# stl_mainboard.net
KiCad netlist of a schematic drawn in EAGLE
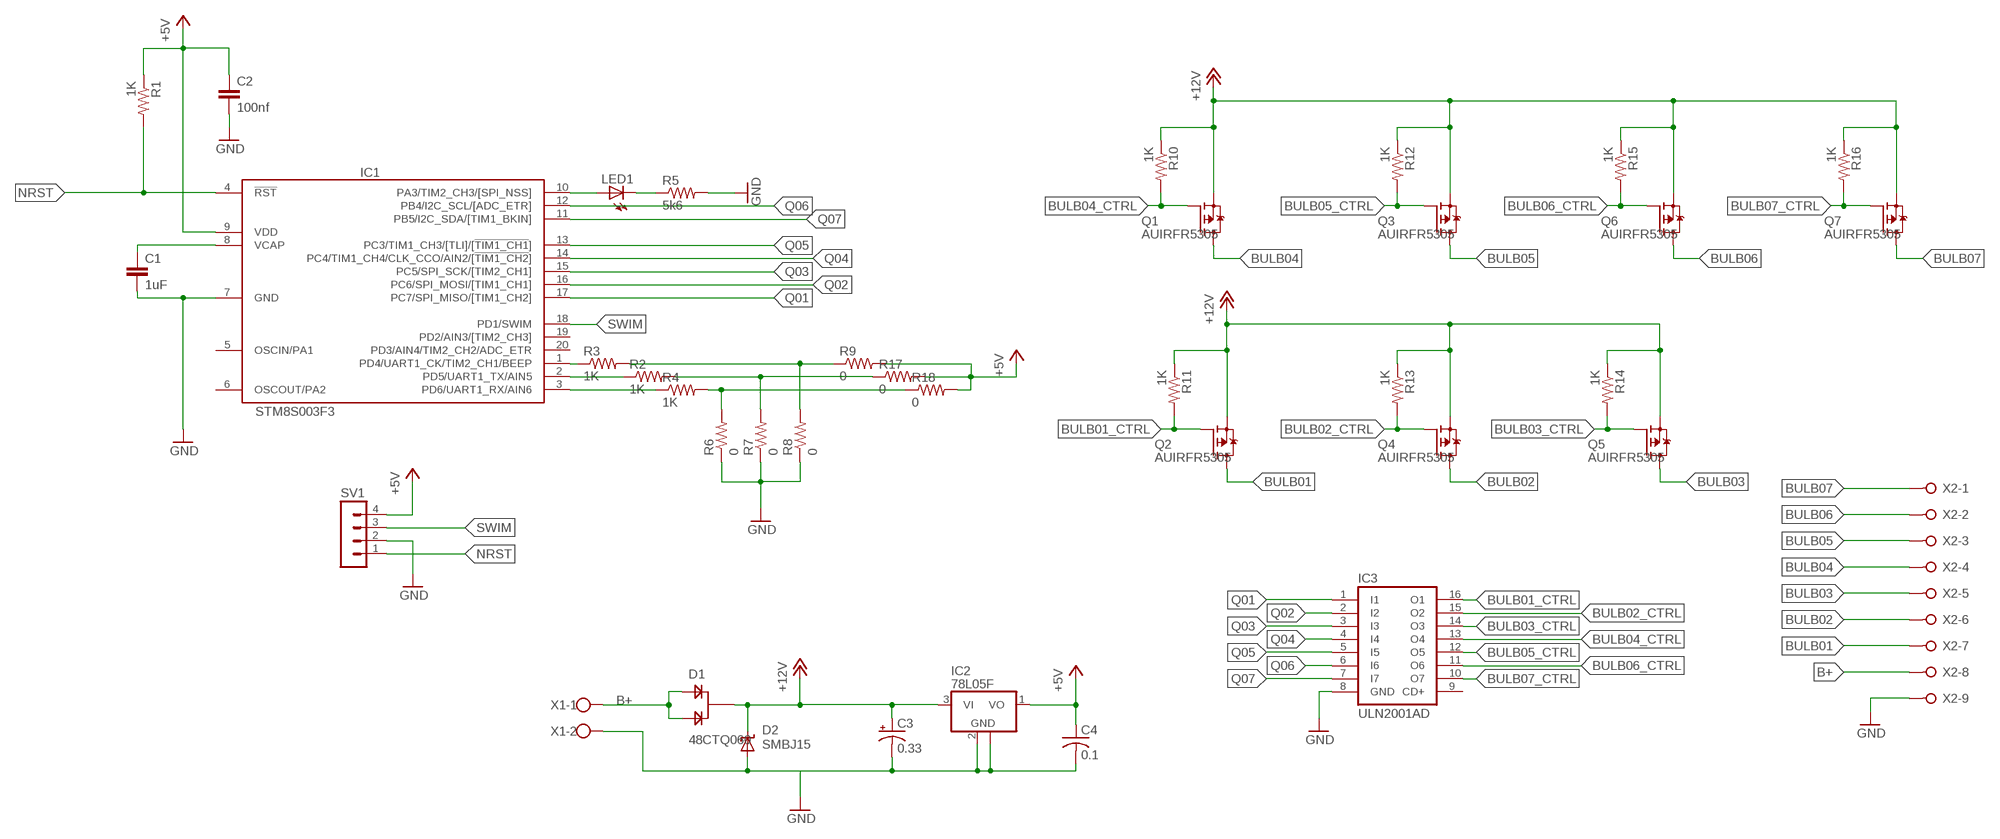
[diagram p0: schematic, sheet 1]

(export (version "E")
  (design (tool "Eeschema 10.0.6"))
  (components
    (comp (ref "C1")
      (value "1uF")
      (footprint "eagle-import:C1206")
      (libsource (lib "eagle-import") (part "C-EUC1206"))
    )
    (comp (ref "C2")
      (value "100nf")
      (footprint "eagle-import:C1206")
      (libsource (lib "eagle-import") (part "C-EUC1206"))
    )
    (comp (ref "C3")
      (value "0.33")
      (footprint "eagle-import:E5-8,5")
      (libsource (lib "eagle-import") (part "CPOL-USE5-8.5"))
    )
    (comp (ref "C4")
      (value "0.1")
      (footprint "eagle-import:C0805")
      (libsource (lib "eagle-import") (part "C-USC0805"))
    )
    (comp (ref "D1")
      (value "48CTQ060")
      (footprint "eagle-import:TO263AB")
      (libsource (lib "eagle-import") (part "48CTQ060"))
    )
    (comp (ref "D2")
      (value "SMBJ15")
      (footprint "eagle-import:SMBJ")
      (libsource (lib "eagle-import") (part "SUPPRESSOR-SMBJ"))
    )
    (comp (ref "IC1")
      (value "STM8S003F3")
      (footprint "eagle-import:TSSOP20")
      (libsource (lib "eagle-import") (part "STM8S003F3"))
    )
    (comp (ref "IC2")
      (value "78L05F")
      (footprint "eagle-import:SOT89")
      (libsource (lib "eagle-import") (part "78LF05"))
    )
    (comp (ref "IC3")
      (value "ULN2001AD")
      (footprint "eagle-import:SO16")
      (libsource (lib "eagle-import") (part "ULN2001AD"))
    )
    (comp (ref "LED1")
      (value "LEDSML1206")
      (footprint "eagle-import:SML1206")
      (libsource (lib "eagle-import") (part "LEDSML1206"))
    )
    (comp (ref "Q1")
      (value "AUIRFR5305")
      (footprint "eagle-import:TO252")
      (libsource (lib "eagle-import") (part "SPD30P06PTO252"))
    )
    (comp (ref "Q2")
      (value "AUIRFR5305")
      (footprint "eagle-import:TO252")
      (libsource (lib "eagle-import") (part "SPD30P06PTO252"))
    )
    (comp (ref "Q3")
      (value "AUIRFR5305")
      (footprint "eagle-import:TO252")
      (libsource (lib "eagle-import") (part "SPD30P06PTO252"))
    )
    (comp (ref "Q4")
      (value "AUIRFR5305")
      (footprint "eagle-import:TO252")
      (libsource (lib "eagle-import") (part "SPD30P06PTO252"))
    )
    (comp (ref "Q5")
      (value "AUIRFR5305")
      (footprint "eagle-import:TO252")
      (libsource (lib "eagle-import") (part "SPD30P06PTO252"))
    )
    (comp (ref "Q6")
      (value "AUIRFR5305")
      (footprint "eagle-import:TO252")
      (libsource (lib "eagle-import") (part "SPD30P06PTO252"))
    )
    (comp (ref "Q7")
      (value "AUIRFR5305")
      (footprint "eagle-import:TO252")
      (libsource (lib "eagle-import") (part "SPD30P06PTO252"))
    )
    (comp (ref "R1")
      (value "1K")
      (footprint "eagle-import:M0805")
      (libsource (lib "eagle-import") (part "R-US_M0805"))
    )
    (comp (ref "R2")
      (value "1K")
      (footprint "eagle-import:M0805")
      (libsource (lib "eagle-import") (part "R-US_M0805"))
    )
    (comp (ref "R3")
      (value "1K")
      (footprint "eagle-import:M0805")
      (libsource (lib "eagle-import") (part "R-US_M0805"))
    )
    (comp (ref "R4")
      (value "1K")
      (footprint "eagle-import:M0805")
      (libsource (lib "eagle-import") (part "R-US_M0805"))
    )
    (comp (ref "R5")
      (value "5k6")
      (footprint "eagle-import:M0805")
      (libsource (lib "eagle-import") (part "R-US_M0805"))
    )
    (comp (ref "R6")
      (value "0")
      (footprint "eagle-import:M0805")
      (libsource (lib "eagle-import") (part "R-US_M0805"))
    )
    (comp (ref "R7")
      (value "0")
      (footprint "eagle-import:M0805")
      (libsource (lib "eagle-import") (part "R-US_M0805"))
    )
    (comp (ref "R8")
      (value "0")
      (footprint "eagle-import:M0805")
      (libsource (lib "eagle-import") (part "R-US_M0805"))
    )
    (comp (ref "R9")
      (value "0")
      (footprint "eagle-import:M0805")
      (libsource (lib "eagle-import") (part "R-US_M0805"))
    )
    (comp (ref "R10")
      (value "1K")
      (footprint "eagle-import:M0805")
      (libsource (lib "eagle-import") (part "R-US_M0805"))
    )
    (comp (ref "R11")
      (value "1K")
      (footprint "eagle-import:M0805")
      (libsource (lib "eagle-import") (part "R-US_M0805"))
    )
    (comp (ref "R12")
      (value "1K")
      (footprint "eagle-import:M0805")
      (libsource (lib "eagle-import") (part "R-US_M0805"))
    )
    (comp (ref "R13")
      (value "1K")
      (footprint "eagle-import:M0805")
      (libsource (lib "eagle-import") (part "R-US_M0805"))
    )
    (comp (ref "R14")
      (value "1K")
      (footprint "eagle-import:M0805")
      (libsource (lib "eagle-import") (part "R-US_M0805"))
    )
    (comp (ref "R15")
      (value "1K")
      (footprint "eagle-import:M0805")
      (libsource (lib "eagle-import") (part "R-US_M0805"))
    )
    (comp (ref "R16")
      (value "1K")
      (footprint "eagle-import:M0805")
      (libsource (lib "eagle-import") (part "R-US_M0805"))
    )
    (comp (ref "R17")
      (value "0")
      (footprint "eagle-import:M0805")
      (libsource (lib "eagle-import") (part "R-US_M0805"))
    )
    (comp (ref "R18")
      (value "0")
      (footprint "eagle-import:M0805")
      (libsource (lib "eagle-import") (part "R-US_M0805"))
    )
    (comp (ref "SV1")
      (value "MA04-1")
      (footprint "eagle-import:MA04-1")
      (libsource (lib "eagle-import") (part "MA04-1"))
    )
    (comp (ref "X1")
      (value "W237-102")
      (footprint "eagle-import:W237-102")
      (fields (field (name "MPN") "237-102"))
      (libsource (lib "eagle-import") (part "W237-102"))
    )
    (comp (ref "X2")
      (value "W237-09P")
      (footprint "eagle-import:W237-9P")
      (libsource (lib "eagle-import") (part "W237-09P"))
    )
  )
  (nets
    (net (code "1") (name "+5V") (class "Default")
      (node (ref "C2") (pin "1") (pinfunction "1_1") (pintype "passive"))
      (node (ref "C4") (pin "1") (pinfunction "1_1") (pintype "passive"))
      (node (ref "IC1") (pin "9") (pinfunction "VDD_9") (pintype "power_in"))
      (node (ref "IC2") (pin "1") (pinfunction "VO_1") (pintype "passive"))
      (node (ref "R1") (pin "1") (pinfunction "1_1") (pintype "passive"))
      (node (ref "R17") (pin "2") (pinfunction "2_2") (pintype "passive"))
      (node (ref "R18") (pin "2") (pinfunction "2_2") (pintype "passive"))
      (node (ref "R9") (pin "2") (pinfunction "2_2") (pintype "passive"))
      (node (ref "SV1") (pin "4") (pinfunction "4_4") (pintype "passive"))
    )
    (net (code "2") (name "+12V") (class "Default")
      (node (ref "C3") (pin "+") (pinfunction "+_+") (pintype "passive"))
      (node (ref "D1") (pin "K") (pinfunction "P$1_K") (pintype "bidirectional"))
      (node (ref "D2") (pin "C") (pinfunction "C_C") (pintype "passive"))
      (node (ref "IC2") (pin "3") (pinfunction "VI_3") (pintype "input"))
      (node (ref "Q1") (pin "2") (pinfunction "S_2") (pintype "passive"))
      (node (ref "Q2") (pin "2") (pinfunction "S_2") (pintype "passive"))
      (node (ref "Q3") (pin "2") (pinfunction "S_2") (pintype "passive"))
      (node (ref "Q4") (pin "2") (pinfunction "S_2") (pintype "passive"))
      (node (ref "Q5") (pin "2") (pinfunction "S_2") (pintype "passive"))
      (node (ref "Q6") (pin "2") (pinfunction "S_2") (pintype "passive"))
      (node (ref "Q7") (pin "2") (pinfunction "S_2") (pintype "passive"))
      (node (ref "R10") (pin "1") (pinfunction "1_1") (pintype "passive"))
      (node (ref "R11") (pin "1") (pinfunction "1_1") (pintype "passive"))
      (node (ref "R12") (pin "1") (pinfunction "1_1") (pintype "passive"))
      (node (ref "R13") (pin "1") (pinfunction "1_1") (pintype "passive"))
      (node (ref "R14") (pin "1") (pinfunction "1_1") (pintype "passive"))
      (node (ref "R15") (pin "1") (pinfunction "1_1") (pintype "passive"))
      (node (ref "R16") (pin "1") (pinfunction "1_1") (pintype "passive"))
    )
    (net (code "3") (name "B+") (class "Default")
      (node (ref "D1") (pin "1") (pinfunction "P$2_1") (pintype "bidirectional"))
      (node (ref "D1") (pin "2") (pinfunction "P$3_2") (pintype "bidirectional"))
      (node (ref "X1") (pin "1") (pinfunction "KL_1") (pintype "passive"))
      (node (ref "X2") (pin "8") (pinfunction "KL_8") (pintype "passive"))
    )
    (net (code "4") (name "BULB01") (class "Default")
      (node (ref "Q2") (pin "3") (pinfunction "D_3") (pintype "passive"))
      (node (ref "X2") (pin "7") (pinfunction "KL_7") (pintype "passive"))
    )
    (net (code "5") (name "BULB01_CTRL") (class "Default")
      (node (ref "IC3") (pin "16") (pinfunction "O1_16") (pintype "open_collector"))
      (node (ref "Q2") (pin "1") (pinfunction "G_1") (pintype "passive"))
      (node (ref "R11") (pin "2") (pinfunction "2_2") (pintype "passive"))
    )
    (net (code "6") (name "BULB02") (class "Default")
      (node (ref "Q4") (pin "3") (pinfunction "D_3") (pintype "passive"))
      (node (ref "X2") (pin "6") (pinfunction "KL_6") (pintype "passive"))
    )
    (net (code "7") (name "BULB02_CTRL") (class "Default")
      (node (ref "IC3") (pin "15") (pinfunction "O2_15") (pintype "open_collector"))
      (node (ref "Q4") (pin "1") (pinfunction "G_1") (pintype "passive"))
      (node (ref "R13") (pin "2") (pinfunction "2_2") (pintype "passive"))
    )
    (net (code "8") (name "BULB03") (class "Default")
      (node (ref "Q5") (pin "3") (pinfunction "D_3") (pintype "passive"))
      (node (ref "X2") (pin "5") (pinfunction "KL_5") (pintype "passive"))
    )
    (net (code "9") (name "BULB03_CTRL") (class "Default")
      (node (ref "IC3") (pin "14") (pinfunction "O3_14") (pintype "open_collector"))
      (node (ref "Q5") (pin "1") (pinfunction "G_1") (pintype "passive"))
      (node (ref "R14") (pin "2") (pinfunction "2_2") (pintype "passive"))
    )
    (net (code "10") (name "BULB04") (class "Default")
      (node (ref "Q1") (pin "3") (pinfunction "D_3") (pintype "passive"))
      (node (ref "X2") (pin "4") (pinfunction "KL_4") (pintype "passive"))
    )
    (net (code "11") (name "BULB04_CTRL") (class "Default")
      (node (ref "IC3") (pin "13") (pinfunction "O4_13") (pintype "open_collector"))
      (node (ref "Q1") (pin "1") (pinfunction "G_1") (pintype "passive"))
      (node (ref "R10") (pin "2") (pinfunction "2_2") (pintype "passive"))
    )
    (net (code "12") (name "BULB05") (class "Default")
      (node (ref "Q3") (pin "3") (pinfunction "D_3") (pintype "passive"))
      (node (ref "X2") (pin "3") (pinfunction "KL_3") (pintype "passive"))
    )
    (net (code "13") (name "BULB05_CTRL") (class "Default")
      (node (ref "IC3") (pin "12") (pinfunction "O5_12") (pintype "open_collector"))
      (node (ref "Q3") (pin "1") (pinfunction "G_1") (pintype "passive"))
      (node (ref "R12") (pin "2") (pinfunction "2_2") (pintype "passive"))
    )
    (net (code "14") (name "BULB06") (class "Default")
      (node (ref "Q6") (pin "3") (pinfunction "D_3") (pintype "passive"))
      (node (ref "X2") (pin "2") (pinfunction "KL_2") (pintype "passive"))
    )
    (net (code "15") (name "BULB06_CTRL") (class "Default")
      (node (ref "IC3") (pin "11") (pinfunction "O6_11") (pintype "open_collector"))
      (node (ref "Q6") (pin "1") (pinfunction "G_1") (pintype "passive"))
      (node (ref "R15") (pin "2") (pinfunction "2_2") (pintype "passive"))
    )
    (net (code "16") (name "BULB07") (class "Default")
      (node (ref "Q7") (pin "3") (pinfunction "D_3") (pintype "passive"))
      (node (ref "X2") (pin "1") (pinfunction "KL_1") (pintype "passive"))
    )
    (net (code "17") (name "BULB07_CTRL") (class "Default")
      (node (ref "IC3") (pin "10") (pinfunction "O7_10") (pintype "open_collector"))
      (node (ref "Q7") (pin "1") (pinfunction "G_1") (pintype "passive"))
      (node (ref "R16") (pin "2") (pinfunction "2_2") (pintype "passive"))
    )
    (net (code "18") (name "GND") (class "Default")
      (node (ref "C1") (pin "2") (pinfunction "2_2") (pintype "passive"))
      (node (ref "C2") (pin "2") (pinfunction "2_2") (pintype "passive"))
      (node (ref "C3") (pin "-") (pinfunction "-_-") (pintype "passive"))
      (node (ref "C4") (pin "2") (pinfunction "2_2") (pintype "passive"))
      (node (ref "D2") (pin "A") (pinfunction "A_A") (pintype "passive"))
      (node (ref "IC1") (pin "7") (pinfunction "GND_7") (pintype "power_in"))
      (node (ref "IC2") (pin "2") (pinfunction "GND_2") (pintype "passive"))
      (node (ref "IC2") (pin "2@1") (pinfunction "GND_2@1") (pintype "passive"))
      (node (ref "IC3") (pin "8") (pinfunction "GND_8") (pintype "power_in"))
      (node (ref "R5") (pin "2") (pinfunction "2_2") (pintype "passive"))
      (node (ref "R6") (pin "1") (pinfunction "1_1") (pintype "passive"))
      (node (ref "R7") (pin "1") (pinfunction "1_1") (pintype "passive"))
      (node (ref "R8") (pin "1") (pinfunction "1_1") (pintype "passive"))
      (node (ref "SV1") (pin "2") (pinfunction "2_2") (pintype "passive"))
      (node (ref "X1") (pin "2") (pinfunction "KL_2") (pintype "passive"))
      (node (ref "X2") (pin "9") (pinfunction "KL_9") (pintype "passive"))
    )
    (net (code "19") (name "NRST") (class "Default")
      (node (ref "IC1") (pin "4") (pinfunction "~{RST}_4") (pintype "input"))
      (node (ref "R1") (pin "2") (pinfunction "2_2") (pintype "passive"))
      (node (ref "SV1") (pin "1") (pinfunction "1_1") (pintype "passive"))
    )
    (net (code "20") (name "Net-(IC1-PA3{slash}TIM2_CH3{slash}[SPI_NSS])") (class "Default")
      (node (ref "IC1") (pin "10") (pinfunction "PA3/TIM2_CH3/[SPI_NSS]_10") (pintype "bidirectional"))
      (node (ref "LED1") (pin "A") (pinfunction "A_A") (pintype "passive"))
    )
    (net (code "21") (name "Net-(IC1-PD4{slash}UART1_CK{slash}TIM2_CH1{slash}BEEP)") (class "Default")
      (node (ref "IC1") (pin "1") (pinfunction "PD4/UART1_CK/TIM2_CH1/BEEP_1") (pintype "bidirectional"))
      (node (ref "R3") (pin "1") (pinfunction "1_1") (pintype "passive"))
    )
    (net (code "22") (name "Net-(IC1-PD5{slash}UART1_TX{slash}AIN5)") (class "Default")
      (node (ref "IC1") (pin "2") (pinfunction "PD5/UART1_TX/AIN5_2") (pintype "bidirectional"))
      (node (ref "R2") (pin "1") (pinfunction "1_1") (pintype "passive"))
    )
    (net (code "23") (name "Net-(IC1-PD6{slash}UART1_RX{slash}AIN6)") (class "Default")
      (node (ref "IC1") (pin "3") (pinfunction "PD6/UART1_RX/AIN6_3") (pintype "bidirectional"))
      (node (ref "R4") (pin "1") (pinfunction "1_1") (pintype "passive"))
    )
    (net (code "24") (name "Net-(IC1-VCAP)") (class "Default")
      (node (ref "C1") (pin "1") (pinfunction "1_1") (pintype "passive"))
      (node (ref "IC1") (pin "8") (pinfunction "VCAP_8") (pintype "power_in"))
    )
    (net (code "25") (name "Net-(LED1-PadC)") (class "Default")
      (node (ref "LED1") (pin "C") (pinfunction "C_C") (pintype "passive"))
      (node (ref "R5") (pin "1") (pinfunction "1_1") (pintype "passive"))
    )
    (net (code "26") (name "Net-(R3-Pad2)") (class "Default")
      (node (ref "R3") (pin "2") (pinfunction "2_2") (pintype "passive"))
      (node (ref "R8") (pin "2") (pinfunction "2_2") (pintype "passive"))
      (node (ref "R9") (pin "1") (pinfunction "1_1") (pintype "passive"))
    )
    (net (code "27") (name "Net-(R17-Pad1)") (class "Default")
      (node (ref "R17") (pin "1") (pinfunction "1_1") (pintype "passive"))
      (node (ref "R2") (pin "2") (pinfunction "2_2") (pintype "passive"))
      (node (ref "R7") (pin "2") (pinfunction "2_2") (pintype "passive"))
    )
    (net (code "28") (name "Net-(R18-Pad1)") (class "Default")
      (node (ref "R18") (pin "1") (pinfunction "1_1") (pintype "passive"))
      (node (ref "R4") (pin "2") (pinfunction "2_2") (pintype "passive"))
      (node (ref "R6") (pin "2") (pinfunction "2_2") (pintype "passive"))
    )
    (net (code "29") (name "Q01") (class "Default")
      (node (ref "IC1") (pin "17") (pinfunction "PC7/SPI_MISO/[TIM1_CH2]_17") (pintype "bidirectional"))
      (node (ref "IC3") (pin "1") (pinfunction "I1_1") (pintype "input"))
    )
    (net (code "30") (name "Q02") (class "Default")
      (node (ref "IC1") (pin "16") (pinfunction "PC6/SPI_MOSI/[TIM1_CH1]_16") (pintype "bidirectional"))
      (node (ref "IC3") (pin "2") (pinfunction "I2_2") (pintype "input"))
    )
    (net (code "31") (name "Q03") (class "Default")
      (node (ref "IC1") (pin "15") (pinfunction "PC5/SPI_SCK/[TIM2_CH1]_15") (pintype "bidirectional"))
      (node (ref "IC3") (pin "3") (pinfunction "I3_3") (pintype "input"))
    )
    (net (code "32") (name "Q04") (class "Default")
      (node (ref "IC1") (pin "14") (pinfunction "PC4/TIM1_CH4/CLK_CCO/AIN2/[~{TIM1_CH2}]_14") (pintype "bidirectional"))
      (node (ref "IC3") (pin "4") (pinfunction "I4_4") (pintype "input"))
    )
    (net (code "33") (name "Q05") (class "Default")
      (node (ref "IC1") (pin "13") (pinfunction "PC3/TIM1_CH3/[TLI]/[~{TIM1_CH1}]_13") (pintype "bidirectional"))
      (node (ref "IC3") (pin "5") (pinfunction "I5_5") (pintype "input"))
    )
    (net (code "34") (name "Q06") (class "Default")
      (node (ref "IC1") (pin "12") (pinfunction "PB4/I2C_SCL/[ADC_ETR]_12") (pintype "bidirectional"))
      (node (ref "IC3") (pin "6") (pinfunction "I6_6") (pintype "input"))
    )
    (net (code "35") (name "Q07") (class "Default")
      (node (ref "IC1") (pin "11") (pinfunction "PB5/I2C_SDA/[TIM1_BKIN]_11") (pintype "bidirectional"))
      (node (ref "IC3") (pin "7") (pinfunction "I7_7") (pintype "input"))
    )
    (net (code "36") (name "SWIM") (class "Default")
      (node (ref "IC1") (pin "18") (pinfunction "PD1/SWIM_18") (pintype "bidirectional"))
      (node (ref "SV1") (pin "3") (pinfunction "3_3") (pintype "passive"))
    )
    (net (code "37") (name "unconnected-(IC1-OSCIN{slash}PA1-Pad5)") (class "Default")
      (node (ref "IC1") (pin "5") (pinfunction "OSCIN/PA1_5") (pintype "bidirectional"))
    )
    (net (code "38") (name "unconnected-(IC1-OSCOUT{slash}PA2-Pad6)") (class "Default")
      (node (ref "IC1") (pin "6") (pinfunction "OSCOUT/PA2_6") (pintype "bidirectional"))
    )
    (net (code "39") (name "unconnected-(IC1-PD2{slash}AIN3{slash}[TIM2_CH3]-Pad19)") (class "Default")
      (node (ref "IC1") (pin "19") (pinfunction "PD2/AIN3/[TIM2_CH3]_19") (pintype "bidirectional"))
    )
    (net (code "40") (name "unconnected-(IC1-PD3{slash}AIN4{slash}TIM2_CH2{slash}ADC_ETR-Pad20)") (class "Default")
      (node (ref "IC1") (pin "20") (pinfunction "PD3/AIN4/TIM2_CH2/ADC_ETR_20") (pintype "bidirectional"))
    )
    (net (code "41") (name "unconnected-(IC3-CD+-Pad9)") (class "Default")
      (node (ref "IC3") (pin "9") (pinfunction "CD+_9") (pintype "passive"))
    )
  )
)
